# rj45-breakout-1_0.net
KiCad netlist of a schematic drawn in EAGLE
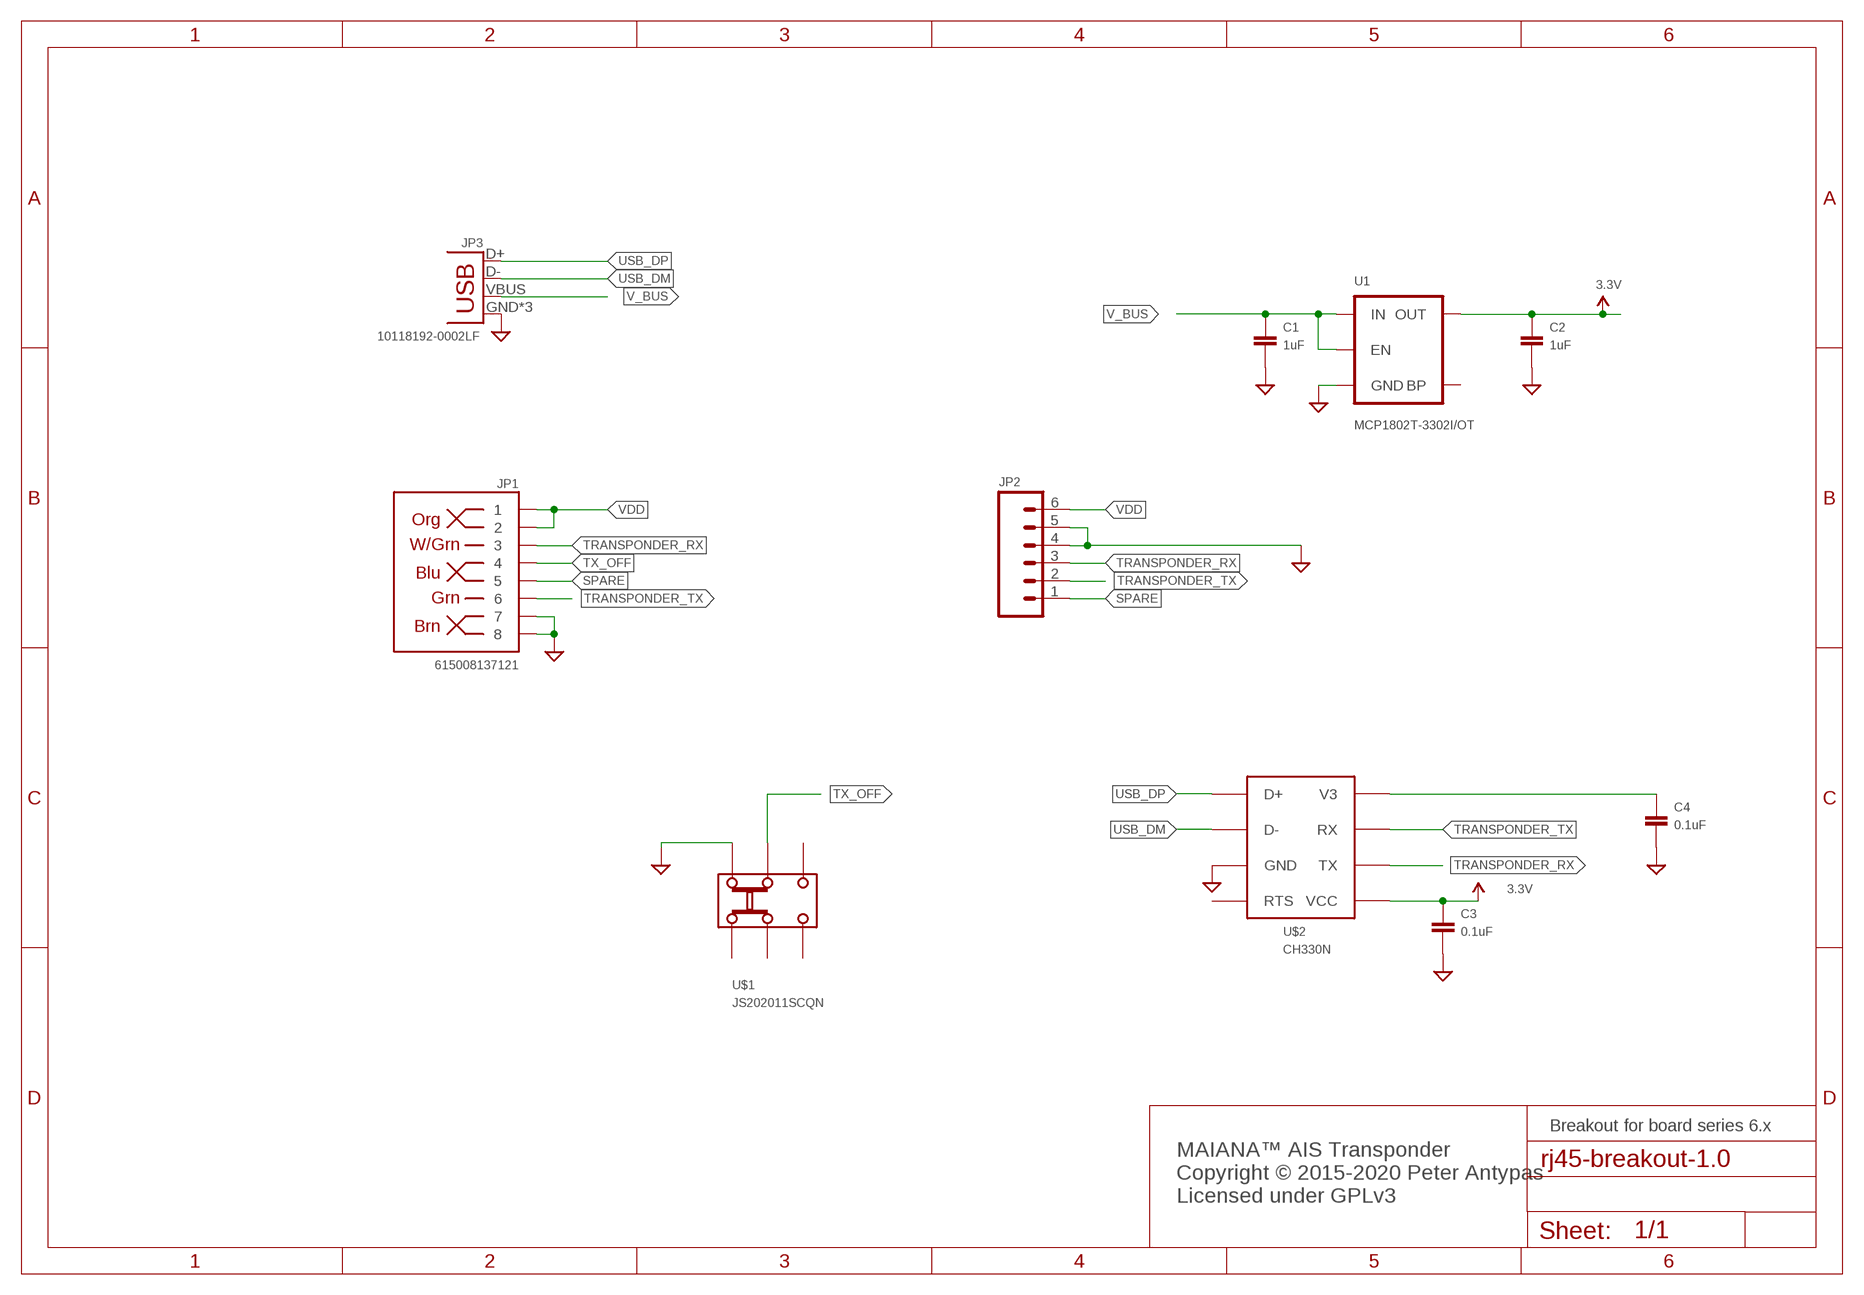
[diagram p0: schematic, sheet 1]

(export (version "E")
  (design (tool "Eeschema 10.0.6"))
  (components
    (comp (ref "C1")
      (value "1uF")
      (footprint "eagle-import:0603")
      (libsource (lib "eagle-import") (part "CAPACITOR0603"))
    )
    (comp (ref "C2")
      (value "1uF")
      (footprint "eagle-import:0603")
      (libsource (lib "eagle-import") (part "CAPACITOR0603"))
    )
    (comp (ref "C3")
      (value "0.1uF")
      (footprint "eagle-import:0603")
      (libsource (lib "eagle-import") (part "CAPACITOR0603"))
    )
    (comp (ref "C4")
      (value "0.1uF")
      (footprint "eagle-import:0603")
      (libsource (lib "eagle-import") (part "CAPACITOR0603"))
    )
    (comp (ref "JP1")
      (value "615008137121")
      (footprint "eagle-import:RJ45-8")
      (libsource (lib "eagle-import") (part "RJ45-8PTH"))
    )
    (comp (ref "JP2")
      (value "M06SILK_FEMALE_PTH")
      (footprint "eagle-import:1X06")
      (libsource (lib "eagle-import") (part "M06SILK_FEMALE_PTH"))
    )
    (comp (ref "JP3")
      (value "10118192-0002LF")
      (footprint "eagle-import:USB-MICROB")
      (libsource (lib "eagle-import") (part "USB-MICROB"))
    )
    (comp (ref "U$1")
      (value "JS202011SCQN")
      (footprint "eagle-import:DPDT-SMD")
      (libsource (lib "eagle-import") (part "JS202011SCQN"))
    )
    (comp (ref "U$2")
      (value "CH330N")
      (footprint "eagle-import:SOIC-8")
      (libsource (lib "eagle-import") (part "CH330N"))
    )
    (comp (ref "U1")
      (value "MCP1802T-3302I/OT")
      (footprint "eagle-import:SOT23-5")
      (libsource (lib "eagle-import") (part "V_REG_LDOSMD"))
    )
  )
  (nets
    (net (code "1") (name "3.3V") (class "Default")
      (node (ref "C2") (pin "P$1") (pinfunction "P$1_P$1") (pintype "bidirectional"))
      (node (ref "C3") (pin "P$1") (pinfunction "P$1_P$1") (pintype "bidirectional"))
      (node (ref "U$2") (pin "5") (pinfunction "VCC_5") (pintype "bidirectional"))
      (node (ref "U1") (pin "5") (pinfunction "OUT_5") (pintype "passive"))
    )
    (net (code "2") (name "GND") (class "Default")
      (node (ref "C1") (pin "P$2") (pinfunction "P$2_P$2") (pintype "bidirectional"))
      (node (ref "C2") (pin "P$2") (pinfunction "P$2_P$2") (pintype "bidirectional"))
      (node (ref "C3") (pin "P$2") (pinfunction "P$2_P$2") (pintype "bidirectional"))
      (node (ref "C4") (pin "P$2") (pinfunction "P$2_P$2") (pintype "bidirectional"))
      (node (ref "JP1") (pin "7") (pinfunction "7_7") (pintype "bidirectional"))
      (node (ref "JP1") (pin "8") (pinfunction "8_8") (pintype "bidirectional"))
      (node (ref "JP2") (pin "4") (pinfunction "4_4") (pintype "passive"))
      (node (ref "JP2") (pin "5") (pinfunction "5_5") (pintype "passive"))
      (node (ref "JP3") (pin "GND") (pinfunction "GND_GND") (pintype "bidirectional"))
      (node (ref "JP3") (pin "MT1") (pinfunction "GND_MT1") (pintype "bidirectional"))
      (node (ref "JP3") (pin "MT2") (pinfunction "GND_MT2") (pintype "bidirectional"))
      (node (ref "U$1") (pin "P$6") (pinfunction "P$6_P$6") (pintype "bidirectional"))
      (node (ref "U$2") (pin "3") (pinfunction "GND_3") (pintype "bidirectional"))
      (node (ref "U1") (pin "2") (pinfunction "GND_2") (pintype "input"))
    )
    (net (code "3") (name "Net-(U$2-V3)") (class "Default")
      (node (ref "C4") (pin "P$1") (pinfunction "P$1_P$1") (pintype "bidirectional"))
      (node (ref "U$2") (pin "8") (pinfunction "V3_8") (pintype "bidirectional"))
    )
    (net (code "4") (name "SPARE") (class "Default")
      (node (ref "JP1") (pin "5") (pinfunction "5_5") (pintype "bidirectional"))
      (node (ref "JP2") (pin "1") (pinfunction "1_1") (pintype "passive"))
    )
    (net (code "5") (name "TRANSPONDER_RX") (class "Default")
      (node (ref "JP1") (pin "3") (pinfunction "3_3") (pintype "bidirectional"))
      (node (ref "JP2") (pin "3") (pinfunction "3_3") (pintype "passive"))
      (node (ref "U$2") (pin "6") (pinfunction "TX_6") (pintype "bidirectional"))
    )
    (net (code "6") (name "TRANSPONDER_TX") (class "Default")
      (node (ref "JP1") (pin "6") (pinfunction "6_6") (pintype "bidirectional"))
      (node (ref "JP2") (pin "2") (pinfunction "2_2") (pintype "passive"))
      (node (ref "U$2") (pin "7") (pinfunction "RX_7") (pintype "bidirectional"))
    )
    (net (code "7") (name "TX_OFF") (class "Default")
      (node (ref "JP1") (pin "4") (pinfunction "4_4") (pintype "bidirectional"))
      (node (ref "U$1") (pin "P$5") (pinfunction "P$5_P$5") (pintype "bidirectional"))
    )
    (net (code "8") (name "USB_DM") (class "Default")
      (node (ref "JP3") (pin "D-") (pinfunction "D-_D-") (pintype "bidirectional"))
      (node (ref "U$2") (pin "2") (pinfunction "D-_2") (pintype "bidirectional"))
    )
    (net (code "9") (name "USB_DP") (class "Default")
      (node (ref "JP3") (pin "D+") (pinfunction "D+_D+") (pintype "bidirectional"))
      (node (ref "U$2") (pin "1") (pinfunction "D+_1") (pintype "bidirectional"))
    )
    (net (code "10") (name "VDD") (class "Default")
      (node (ref "JP1") (pin "1") (pinfunction "1_1") (pintype "bidirectional"))
      (node (ref "JP1") (pin "2") (pinfunction "2_2") (pintype "bidirectional"))
      (node (ref "JP2") (pin "6") (pinfunction "6_6") (pintype "passive"))
    )
    (net (code "11") (name "V_BUS") (class "Default")
      (node (ref "C1") (pin "P$1") (pinfunction "P$1_P$1") (pintype "bidirectional"))
      (node (ref "JP3") (pin "VBUS") (pinfunction "VBUS_VBUS") (pintype "bidirectional"))
      (node (ref "U1") (pin "1") (pinfunction "IN_1") (pintype "input"))
      (node (ref "U1") (pin "3") (pinfunction "EN_3") (pintype "input"))
    )
    (net (code "12") (name "unconnected-(U$1-PadP$1)") (class "Default")
      (node (ref "U$1") (pin "P$1") (pinfunction "P$1_P$1") (pintype "bidirectional"))
    )
    (net (code "13") (name "unconnected-(U$1-PadP$2)") (class "Default")
      (node (ref "U$1") (pin "P$2") (pinfunction "P$2_P$2") (pintype "bidirectional"))
    )
    (net (code "14") (name "unconnected-(U$1-PadP$3)") (class "Default")
      (node (ref "U$1") (pin "P$3") (pinfunction "P$3_P$3") (pintype "bidirectional"))
    )
    (net (code "15") (name "unconnected-(U$1-PadP$4)") (class "Default")
      (node (ref "U$1") (pin "P$4") (pinfunction "P$4_P$4") (pintype "bidirectional"))
    )
    (net (code "16") (name "unconnected-(U$2-RTS-Pad4)") (class "Default")
      (node (ref "U$2") (pin "4") (pinfunction "RTS_4") (pintype "bidirectional"))
    )
    (net (code "17") (name "unconnected-(U1-BP-Pad4)") (class "Default")
      (node (ref "U1") (pin "4") (pinfunction "BP_4") (pintype "input"))
    )
  )
)
